# SCREEN_SWITCH.net
KiCad netlist of a schematic drawn in Altium Designer
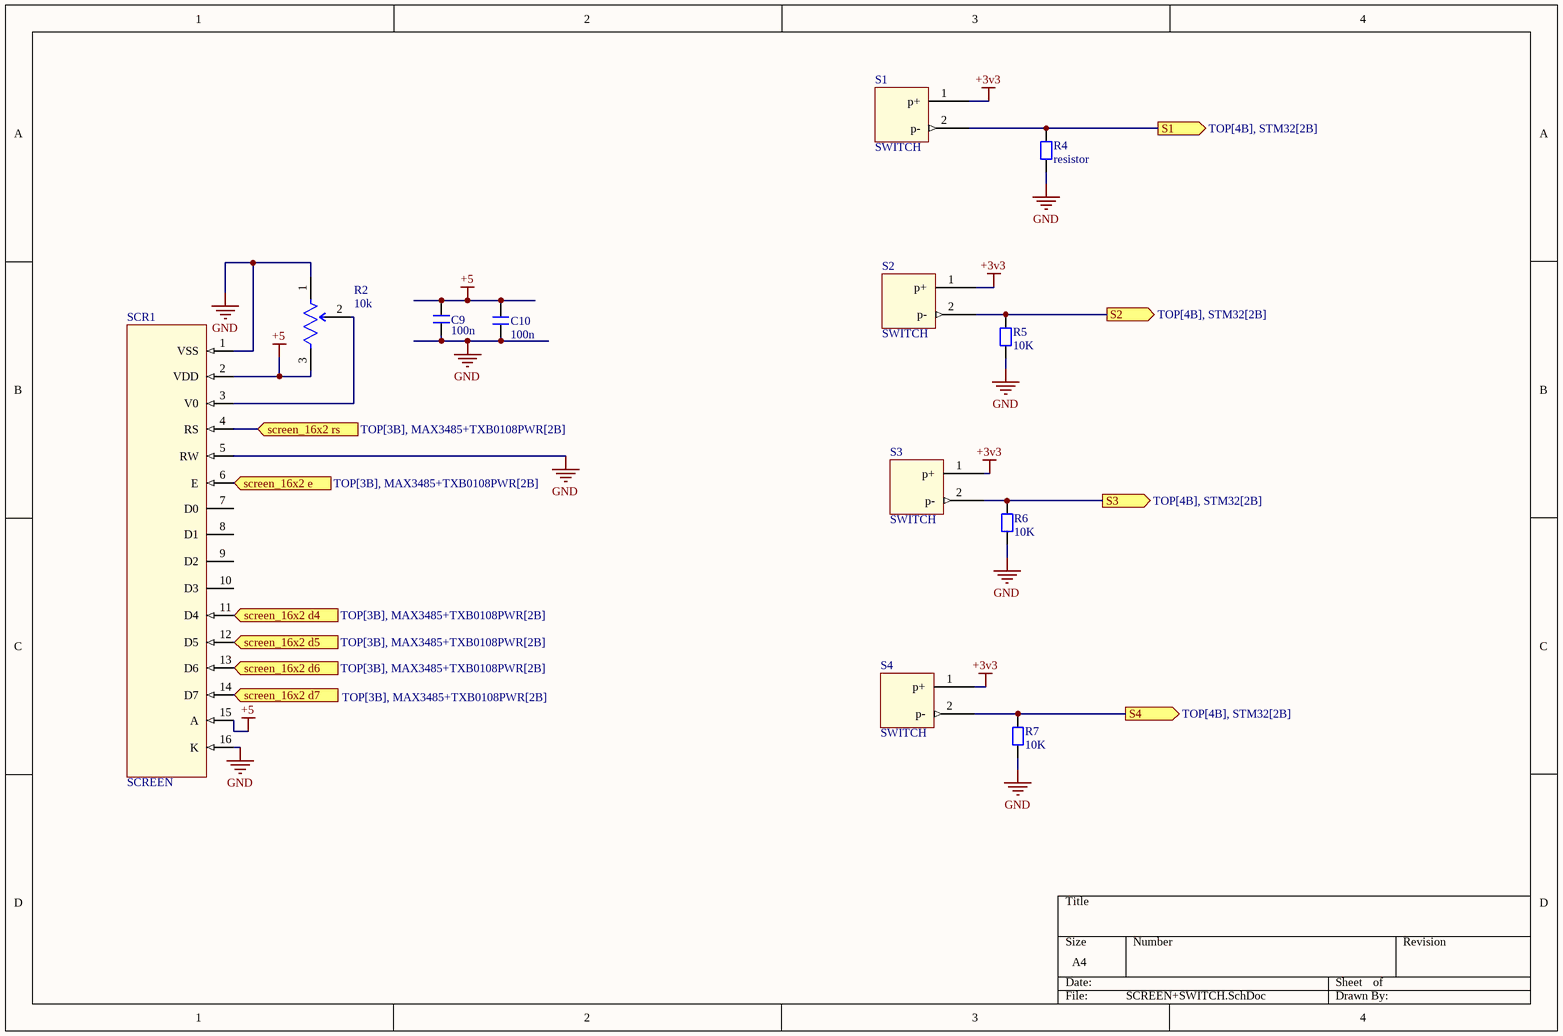
[diagram p0: SCREEN+SWITCH.SchDoc]

(export (version "E")
  (design (tool "Eeschema 10.0.6"))
  (components
    (comp (ref "C9") (value "100n") (footprint "0805") (libsource (lib "capacitor") (part "capacitor")))
    (comp (ref "C10") (value "100n") (footprint "0805") (libsource (lib "capacitor") (part "capacitor")))
    (comp (ref "R2")
      (value "10k")
      (footprint "potentiometer")
      (libsource (lib "potentiometer") (part "potentiometer"))
    )
    (comp (ref "R4") (value "resistor") (footprint "0805") (libsource (lib "resistor") (part "resistor")))
    (comp (ref "R5") (value "10K") (footprint "0805") (libsource (lib "resistor") (part "resistor")))
    (comp (ref "R6") (value "10K") (footprint "0805") (libsource (lib "resistor") (part "resistor")))
    (comp (ref "R7") (value "10K") (footprint "0805") (libsource (lib "resistor") (part "resistor")))
    (comp (ref "S1") (value "SWITCH") (footprint "SWITCh") (libsource (lib "SWITCH") (part "SWITCH")))
    (comp (ref "S2") (value "SWITCH") (footprint "SWITCh") (libsource (lib "SWITCH") (part "SWITCH")))
    (comp (ref "S3") (value "SWITCH") (footprint "SWITCh") (libsource (lib "SWITCH") (part "SWITCH")))
    (comp (ref "S4") (value "SWITCH") (footprint "SWITCh") (libsource (lib "SWITCH") (part "SWITCH")))
    (comp (ref "SCR1") (value "SCREEN") (footprint "SCREEN") (libsource (lib "SCREEN") (part "SCREEN")))
  )
  (nets
    (net (code "1") (name "+3v3") (class "Default")
      (node (ref "S1") (pin "1") (pinfunction "p+_1") (pintype "passive"))
      (node (ref "S2") (pin "1") (pinfunction "p+_1") (pintype "passive"))
      (node (ref "S3") (pin "1") (pinfunction "p+_1") (pintype "passive"))
      (node (ref "S4") (pin "1") (pinfunction "p+_1") (pintype "passive"))
    )
    (net (code "2") (name "+5") (class "Default")
      (node (ref "C10") (pin "1") (pinfunction "1_1") (pintype "passive"))
      (node (ref "C9") (pin "1") (pinfunction "1_1") (pintype "passive"))
      (node (ref "R2") (pin "3") (pinfunction "CW_3") (pintype "passive"))
      (node (ref "SCR1") (pin "15") (pinfunction "A_15") (pintype "input"))
      (node (ref "SCR1") (pin "2") (pinfunction "VDD_2") (pintype "input"))
    )
    (net (code "3") (name "/S1") (class "Default")
      (node (ref "R4") (pin "1") (pinfunction "1_1") (pintype "passive"))
      (node (ref "S1") (pin "2") (pinfunction "p-_2") (pintype "output"))
    )
    (net (code "4") (name "/S2") (class "Default")
      (node (ref "R5") (pin "1") (pinfunction "1_1") (pintype "passive"))
      (node (ref "S2") (pin "2") (pinfunction "p-_2") (pintype "output"))
    )
    (net (code "5") (name "/S3") (class "Default")
      (node (ref "R6") (pin "1") (pinfunction "1_1") (pintype "passive"))
      (node (ref "S3") (pin "2") (pinfunction "p-_2") (pintype "output"))
    )
    (net (code "6") (name "/S4") (class "Default")
      (node (ref "R7") (pin "1") (pinfunction "1_1") (pintype "passive"))
      (node (ref "S4") (pin "2") (pinfunction "p-_2") (pintype "output"))
    )
    (net (code "7") (name "/screen_16x2 d4") (class "Default")
      (node (ref "SCR1") (pin "11") (pinfunction "D4_11") (pintype "input"))
    )
    (net (code "8") (name "/screen_16x2 d5") (class "Default")
      (node (ref "SCR1") (pin "12") (pinfunction "D5_12") (pintype "input"))
    )
    (net (code "9") (name "/screen_16x2 d6") (class "Default")
      (node (ref "SCR1") (pin "13") (pinfunction "D6_13") (pintype "input"))
    )
    (net (code "10") (name "/screen_16x2 d7") (class "Default")
      (node (ref "SCR1") (pin "14") (pinfunction "D7_14") (pintype "input"))
    )
    (net (code "11") (name "/screen_16x2 e") (class "Default")
      (node (ref "SCR1") (pin "6") (pinfunction "E_6") (pintype "input"))
    )
    (net (code "12") (name "/screen_16x2 rs") (class "Default")
      (node (ref "SCR1") (pin "4") (pinfunction "RS_4") (pintype "input"))
    )
    (net (code "13") (name "GND") (class "Default")
      (node (ref "C10") (pin "2") (pintype "passive"))
      (node (ref "C9") (pin "2") (pintype "passive"))
      (node (ref "R2") (pin "1") (pinfunction "CCW_1") (pintype "passive"))
      (node (ref "R4") (pin "2") (pinfunction "2_2") (pintype "passive"))
      (node (ref "R5") (pin "2") (pinfunction "2_2") (pintype "passive"))
      (node (ref "R6") (pin "2") (pinfunction "2_2") (pintype "passive"))
      (node (ref "R7") (pin "2") (pinfunction "2_2") (pintype "passive"))
      (node (ref "SCR1") (pin "1") (pinfunction "VSS_1") (pintype "input"))
      (node (ref "SCR1") (pin "16") (pinfunction "K_16") (pintype "input"))
      (node (ref "SCR1") (pin "5") (pinfunction "RW_5") (pintype "input"))
    )
    (net (code "14") (name "Net-(R2-WIPER)") (class "Default")
      (node (ref "R2") (pin "2") (pinfunction "WIPER_2") (pintype "passive"))
      (node (ref "SCR1") (pin "3") (pinfunction "V0_3") (pintype "input"))
    )
    (net (code "15") (name "unconnected-(SCR1-D0-Pad7)") (class "Default")
      (node (ref "SCR1") (pin "7") (pinfunction "D0_7") (pintype "passive"))
    )
    (net (code "16") (name "unconnected-(SCR1-D1-Pad8)") (class "Default")
      (node (ref "SCR1") (pin "8") (pinfunction "D1_8") (pintype "passive"))
    )
    (net (code "17") (name "unconnected-(SCR1-D2-Pad9)") (class "Default")
      (node (ref "SCR1") (pin "9") (pinfunction "D2_9") (pintype "passive"))
    )
    (net (code "18") (name "unconnected-(SCR1-D3-Pad10)") (class "Default")
      (node (ref "SCR1") (pin "10") (pinfunction "D3_10") (pintype "passive"))
    )
  )
)
